# temp_sensor.net
KiCad netlist of a schematic drawn in EAGLE
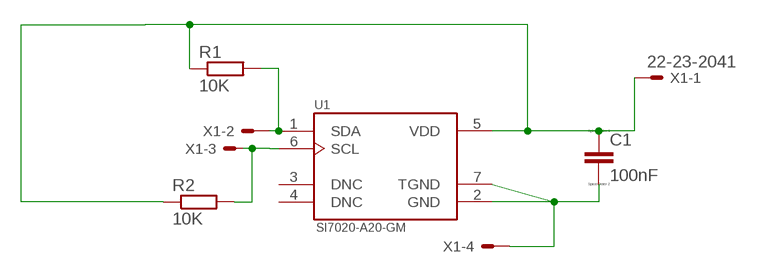
[diagram p0: schematic, sheet 1]

(export (version "E")
  (design (tool "Eeschema 10.0.6"))
  (components
    (comp (ref "C1")
      (value "100nF")
      (footprint "eagle-import:C0603")
      (libsource (lib "eagle-import") (part "CC0603"))
    )
    (comp (ref "R1")
      (value "10K")
      (footprint "eagle-import:R0402")
      (libsource (lib "eagle-import") (part "R-EU_R0402"))
    )
    (comp (ref "R2")
      (value "10K")
      (footprint "eagle-import:R0402")
      (libsource (lib "eagle-import") (part "R-EU_R0402"))
    )
    (comp (ref "U1")
      (value "SI7020-A20-GM")
      (footprint "eagle-import:SON100P300X300X80-7N")
      (fields (field (name "MF") "Silicon Labs"))
      (libsource (lib "eagle-import") (part "SI7020-A20-GM"))
    )
    (comp (ref "X1")
      (value "22-23-2041")
      (footprint "eagle-import:22-23-2041")
      (fields (field (name "MF") "MOLEX"))
      (libsource (lib "eagle-import") (part "22-23-2041"))
    )
  )
  (nets
    (net (code "1") (name "Net-(U1-GND)") (class "Default")
      (node (ref "C1") (pin "2") (pinfunction "2_2") (pintype "passive"))
      (node (ref "U1") (pin "2") (pinfunction "GND_2") (pintype "power_in"))
      (node (ref "U1") (pin "7") (pinfunction "TGND_7") (pintype "bidirectional"))
      (node (ref "X1") (pin "4") (pinfunction "S_4") (pintype "passive"))
    )
    (net (code "2") (name "Net-(U1-SCL)") (class "Default")
      (node (ref "R2") (pin "2") (pinfunction "2_2") (pintype "passive"))
      (node (ref "U1") (pin "6") (pinfunction "SCL_6") (pintype "bidirectional"))
      (node (ref "X1") (pin "3") (pinfunction "S_3") (pintype "passive"))
    )
    (net (code "3") (name "Net-(U1-SDA)") (class "Default")
      (node (ref "R1") (pin "2") (pinfunction "2_2") (pintype "passive"))
      (node (ref "U1") (pin "1") (pinfunction "SDA_1") (pintype "bidirectional"))
      (node (ref "X1") (pin "2") (pinfunction "S_2") (pintype "passive"))
    )
    (net (code "4") (name "Net-(U1-VDD)") (class "Default")
      (node (ref "C1") (pin "1") (pinfunction "1_1") (pintype "passive"))
      (node (ref "R1") (pin "1") (pinfunction "1_1") (pintype "passive"))
      (node (ref "R2") (pin "1") (pinfunction "1_1") (pintype "passive"))
      (node (ref "U1") (pin "5") (pinfunction "VDD_5") (pintype "power_in"))
      (node (ref "X1") (pin "1") (pinfunction "S_1") (pintype "passive"))
    )
    (net (code "5") (name "unconnected-(U1-DNC-Pad3)") (class "Default")
      (node (ref "U1") (pin "3") (pinfunction "DNC_3") (pintype "bidirectional"))
    )
    (net (code "6") (name "unconnected-(U1-DNC-Pad4)") (class "Default")
      (node (ref "U1") (pin "4") (pinfunction "DNC_4") (pintype "bidirectional"))
    )
  )
)
